# TrackerS_onecznyv2.net
KiCad netlist of a schematic drawn in EAGLE
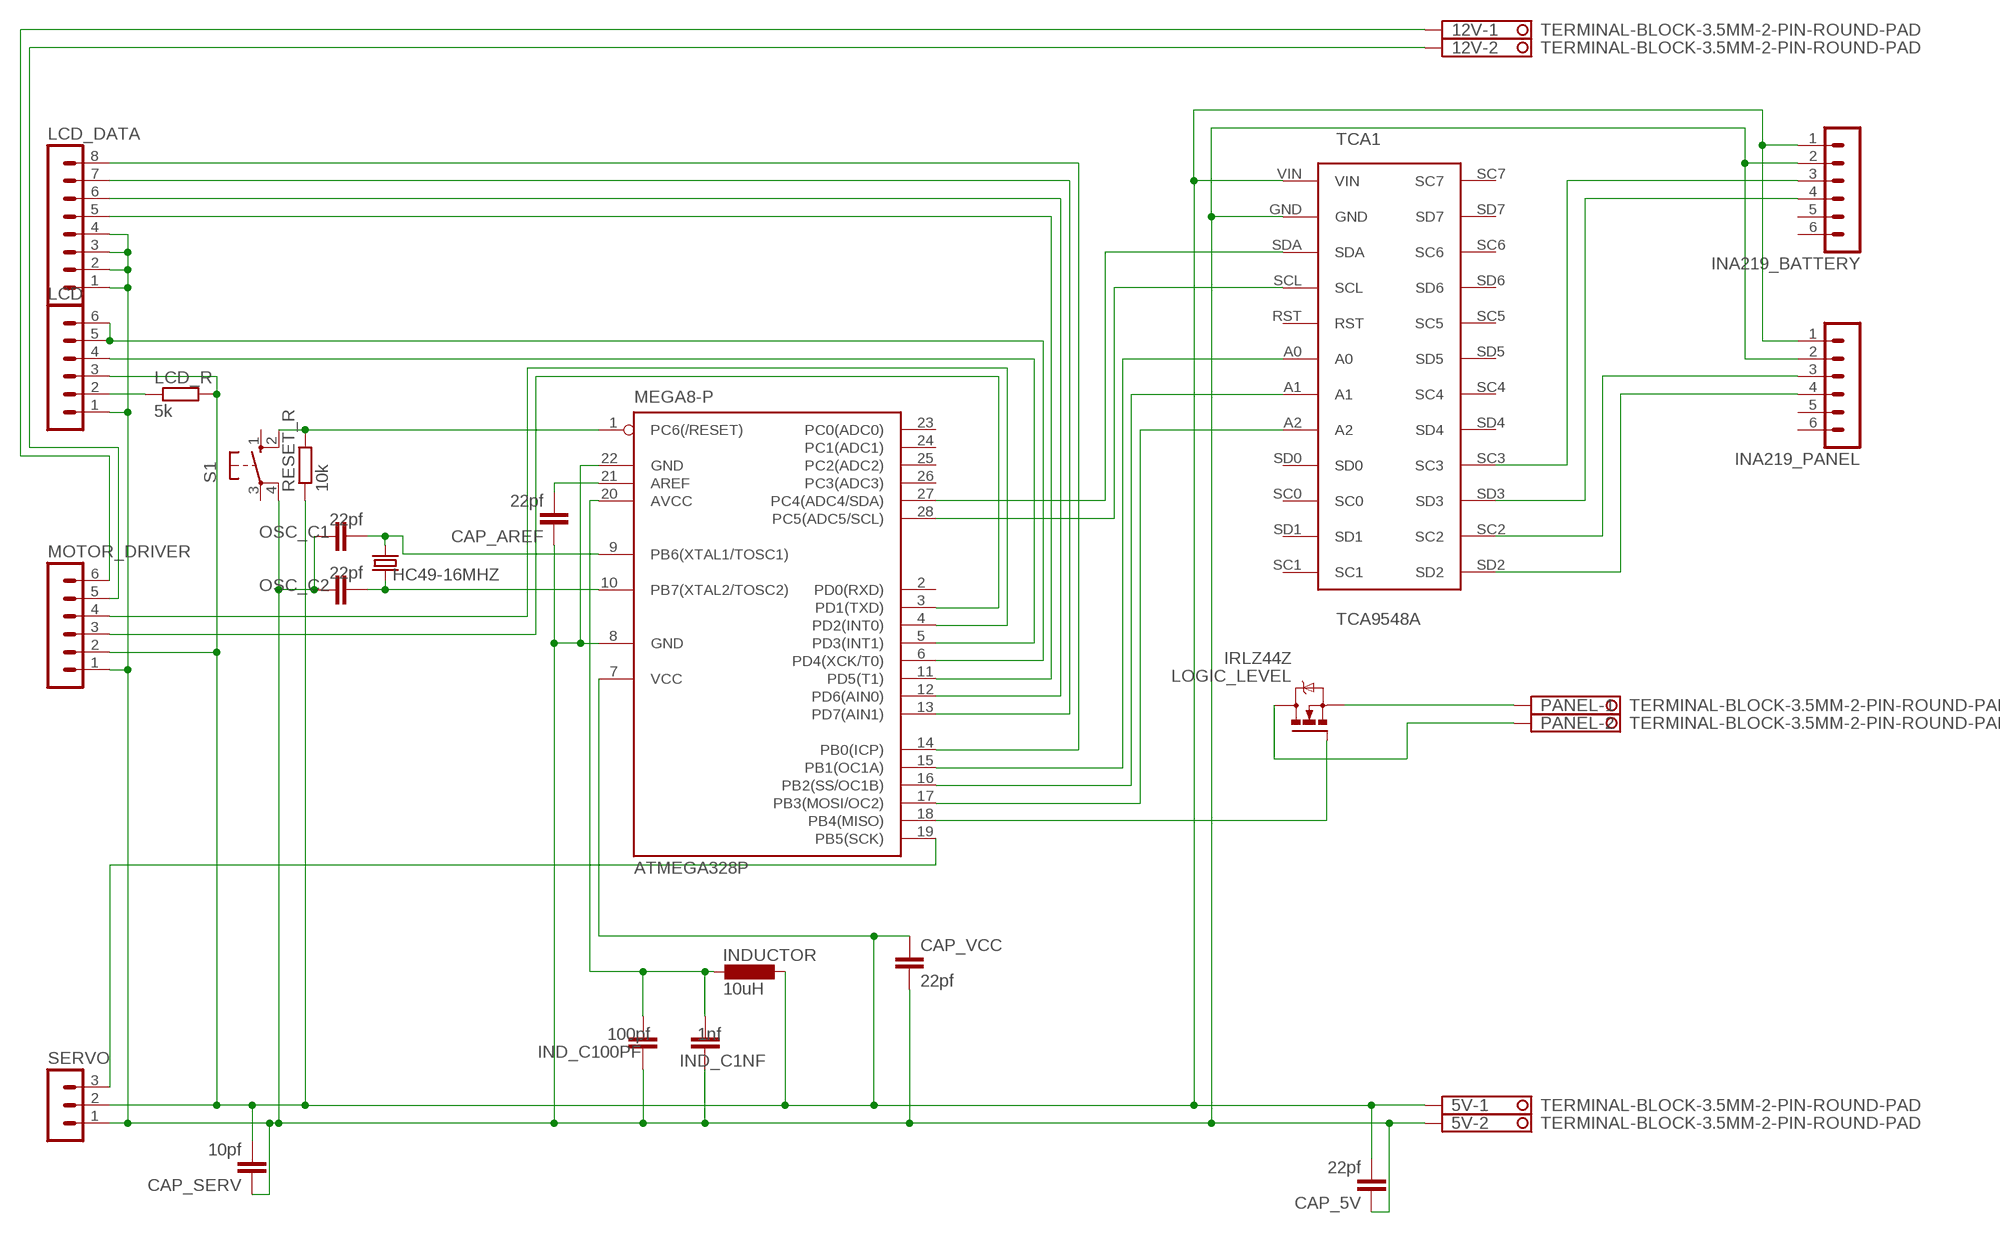
[diagram p0: schematic, sheet 1]

(export (version "E")
  (design (tool "Eeschema 10.0.6"))
  (components
    (comp (ref "5V")
      (value "TERMINAL-BLOCK-3.5MM-2-PIN-ROUND-PAD")
      (footprint "eagle-import:TERMINAL-BLOCK-2-PIN-3.5MM-ROUND-PAD")
      (libsource (lib "eagle-import") (part "TERMINAL-BLOCK-3.5MM-2-PIN-ROUND-PAD"))
    )
    (comp (ref "12V")
      (value "TERMINAL-BLOCK-3.5MM-2-PIN-ROUND-PAD")
      (footprint "eagle-import:TERMINAL-BLOCK-2-PIN-3.5MM-ROUND-PAD")
      (libsource (lib "eagle-import") (part "TERMINAL-BLOCK-3.5MM-2-PIN-ROUND-PAD"))
    )
    (comp (ref "ATMEGA328P")
      (value "MEGA8-P")
      (footprint "eagle-import:DIL28-3")
      (libsource (lib "eagle-import") (part "MEGA8-P"))
    )
    (comp (ref "CAP_5V")
      (value "22pf")
      (footprint "eagle-import:C025-024X044")
      (libsource (lib "eagle-import") (part "C-EU025-024X044"))
    )
    (comp (ref "CAP_AREF")
      (value "22pf")
      (footprint "eagle-import:C025-024X044")
      (libsource (lib "eagle-import") (part "C-EU025-024X044"))
    )
    (comp (ref "CAP_SERV")
      (value "10pf")
      (footprint "eagle-import:C025-024X044")
      (libsource (lib "eagle-import") (part "C-EU025-024X044"))
    )
    (comp (ref "CAP_VCC")
      (value "22pf")
      (footprint "eagle-import:C025-024X044")
      (libsource (lib "eagle-import") (part "C-EU025-024X044"))
    )
    (comp (ref "HC49-16MHZ")
      (value "CRYTALHC49S")
      (footprint "eagle-import:HC49_S")
      (libsource (lib "eagle-import") (part "CRYTALHC49S"))
    )
    (comp (ref "INA219_BATTERY")
      (value "MA06-1")
      (footprint "eagle-import:MA06-1")
      (libsource (lib "eagle-import") (part "con-lstb_162_MA06-1"))
    )
    (comp (ref "INA219_PANEL")
      (value "MA06-1")
      (footprint "eagle-import:MA06-1")
      (libsource (lib "eagle-import") (part "con-lstb_162_MA06-1"))
    )
    (comp (ref "INDUCTOR")
      (value "10uH")
      (footprint "eagle-import:0207_2V")
      (libsource (lib "eagle-import") (part "L-EU0207/2V"))
    )
    (comp (ref "IND_C1NF")
      (value "1nf")
      (footprint "eagle-import:C025-024X044")
      (libsource (lib "eagle-import") (part "C-EU025-024X044"))
    )
    (comp (ref "IND_C100PF")
      (value "100pf")
      (footprint "eagle-import:C025-024X044")
      (libsource (lib "eagle-import") (part "C-EU025-024X044"))
    )
    (comp (ref "LCD")
      (value "MA06-1")
      (footprint "eagle-import:MA06-1")
      (libsource (lib "eagle-import") (part "MA06-1"))
    )
    (comp (ref "LCD_DATA")
      (value "MA08-1")
      (footprint "eagle-import:MA08-1")
      (libsource (lib "eagle-import") (part "MA08-1"))
    )
    (comp (ref "LCD_R")
      (value "5k")
      (footprint "eagle-import:0207_2V")
      (libsource (lib "eagle-import") (part "R-EU_0207/2V"))
    )
    (comp (ref "LOGIC_LEVEL")
      (value "IRLZ44Z")
      (footprint "eagle-import:TO220BH")
      (libsource (lib "eagle-import") (part "IRLZ44Z"))
    )
    (comp (ref "MOTOR_DRIVER")
      (value "MA06-1")
      (footprint "eagle-import:MA06-1")
      (libsource (lib "eagle-import") (part "MA06-1"))
    )
    (comp (ref "OSC_C1")
      (value "22pf")
      (footprint "eagle-import:C025-024X044")
      (libsource (lib "eagle-import") (part "C-EU025-024X044"))
    )
    (comp (ref "OSC_C2")
      (value "22pf")
      (footprint "eagle-import:C025-024X044")
      (libsource (lib "eagle-import") (part "C-EU025-024X044"))
    )
    (comp (ref "PANEL")
      (value "TERMINAL-BLOCK-3.5MM-2-PIN-ROUND-PAD")
      (footprint "eagle-import:TERMINAL-BLOCK-2-PIN-3.5MM-ROUND-PAD")
      (libsource (lib "eagle-import") (part "TERMINAL-BLOCK-3.5MM-2-PIN-ROUND-PAD"))
    )
    (comp (ref "RESET_R")
      (value "10k")
      (footprint "eagle-import:0207_2V")
      (libsource (lib "eagle-import") (part "R-EU_0207/2V"))
    )
    (comp (ref "S1")
      (value "10-XX")
      (footprint "eagle-import:B3F-10XX")
      (fields (field (name "MPN") "B3F-1000"))
      (libsource (lib "eagle-import") (part "10-XX"))
    )
    (comp (ref "SERVO")
      (value "MA03-1")
      (footprint "eagle-import:MA03-1")
      (libsource (lib "eagle-import") (part "MA03-1"))
    )
    (comp (ref "TCA1")
      (value "TCA9548A")
      (footprint "eagle-import:TCA9548A")
      (libsource (lib "eagle-import") (part "TCA9548A"))
    )
  )
  (nets
    (net (code "1") (name "Net-(5VA-K)") (class "Default")
      (node (ref "5V") (pin "1") (pinfunction "K_1") (pintype "passive"))
      (node (ref "ATMEGA328P") (pin "7") (pinfunction "VCC_7") (pintype "power_in"))
      (node (ref "CAP_5V") (pin "2") (pinfunction "2_2") (pintype "passive"))
      (node (ref "CAP_SERV") (pin "2") (pinfunction "2_2") (pintype "passive"))
      (node (ref "CAP_VCC") (pin "1") (pinfunction "1_1") (pintype "passive"))
      (node (ref "INA219_BATTERY") (pin "1") (pinfunction "1_1") (pintype "passive"))
      (node (ref "INA219_PANEL") (pin "1") (pinfunction "1_1") (pintype "passive"))
      (node (ref "INDUCTOR") (pin "1") (pinfunction "1_1") (pintype "passive"))
      (node (ref "LCD") (pin "3") (pinfunction "3_3") (pintype "passive"))
      (node (ref "LCD_R") (pin "2") (pinfunction "2_2") (pintype "passive"))
      (node (ref "MOTOR_DRIVER") (pin "2") (pinfunction "2_2") (pintype "passive"))
      (node (ref "RESET_R") (pin "1") (pinfunction "1_1") (pintype "passive"))
      (node (ref "SERVO") (pin "2") (pinfunction "2_2") (pintype "passive"))
      (node (ref "TCA1") (pin "VIN") (pinfunction "VIN_VIN") (pintype "bidirectional"))
    )
    (net (code "2") (name "Net-(5VB-K)") (class "Default")
      (node (ref "5V") (pin "2") (pinfunction "K_2") (pintype "passive"))
      (node (ref "ATMEGA328P") (pin "22") (pinfunction "GND_22") (pintype "power_in"))
      (node (ref "ATMEGA328P") (pin "8") (pinfunction "GND_8") (pintype "power_in"))
      (node (ref "CAP_5V") (pin "1") (pinfunction "1_1") (pintype "passive"))
      (node (ref "CAP_AREF") (pin "1") (pinfunction "1_1") (pintype "passive"))
      (node (ref "CAP_SERV") (pin "1") (pinfunction "1_1") (pintype "passive"))
      (node (ref "CAP_VCC") (pin "2") (pinfunction "2_2") (pintype "passive"))
      (node (ref "INA219_BATTERY") (pin "2") (pinfunction "2_2") (pintype "passive"))
      (node (ref "INA219_PANEL") (pin "2") (pinfunction "2_2") (pintype "passive"))
      (node (ref "IND_C100PF") (pin "1") (pinfunction "1_1") (pintype "passive"))
      (node (ref "IND_C1NF") (pin "1") (pinfunction "1_1") (pintype "passive"))
      (node (ref "LCD") (pin "1") (pinfunction "1_1") (pintype "passive"))
      (node (ref "LCD_DATA") (pin "1") (pinfunction "1_1") (pintype "passive"))
      (node (ref "LCD_DATA") (pin "2") (pinfunction "2_2") (pintype "passive"))
      (node (ref "LCD_DATA") (pin "3") (pinfunction "3_3") (pintype "passive"))
      (node (ref "LCD_DATA") (pin "4") (pinfunction "4_4") (pintype "passive"))
      (node (ref "MOTOR_DRIVER") (pin "1") (pinfunction "1_1") (pintype "passive"))
      (node (ref "OSC_C1") (pin "1") (pinfunction "1_1") (pintype "passive"))
      (node (ref "OSC_C2") (pin "1") (pinfunction "1_1") (pintype "passive"))
      (node (ref "S1") (pin "4") (pinfunction "P1_4") (pintype "passive"))
      (node (ref "SERVO") (pin "1") (pinfunction "1_1") (pintype "passive"))
      (node (ref "TCA1") (pin "GND") (pinfunction "GND_GND") (pintype "bidirectional"))
    )
    (net (code "3") (name "Net-(12VA-K)") (class "Default")
      (node (ref "12V") (pin "1") (pinfunction "K_1") (pintype "passive"))
      (node (ref "MOTOR_DRIVER") (pin "6") (pinfunction "6_6") (pintype "passive"))
    )
    (net (code "4") (name "Net-(12VB-K)") (class "Default")
      (node (ref "12V") (pin "2") (pinfunction "K_2") (pintype "passive"))
      (node (ref "MOTOR_DRIVER") (pin "5") (pinfunction "5_5") (pintype "passive"))
    )
    (net (code "5") (name "Net-(ATMEGA328P-AREF)") (class "Default")
      (node (ref "ATMEGA328P") (pin "21") (pinfunction "AREF_21") (pintype "passive"))
      (node (ref "CAP_AREF") (pin "2") (pinfunction "2_2") (pintype "passive"))
    )
    (net (code "6") (name "Net-(ATMEGA328P-AVCC)") (class "Default")
      (node (ref "ATMEGA328P") (pin "20") (pinfunction "AVCC_20") (pintype "power_in"))
      (node (ref "INDUCTOR") (pin "2") (pinfunction "2_2") (pintype "passive"))
      (node (ref "IND_C100PF") (pin "2") (pinfunction "2_2") (pintype "passive"))
      (node (ref "IND_C1NF") (pin "2") (pinfunction "2_2") (pintype "passive"))
    )
    (net (code "7") (name "Net-(ATMEGA328P-PB0(ICP))") (class "Default")
      (node (ref "ATMEGA328P") (pin "14") (pinfunction "PB0(ICP)_14") (pintype "bidirectional"))
      (node (ref "LCD_DATA") (pin "8") (pinfunction "8_8") (pintype "passive"))
    )
    (net (code "8") (name "Net-(ATMEGA328P-PB1(OC1A))") (class "Default")
      (node (ref "ATMEGA328P") (pin "15") (pinfunction "PB1(OC1A)_15") (pintype "bidirectional"))
      (node (ref "TCA1") (pin "A0") (pinfunction "A0_A0") (pintype "bidirectional"))
    )
    (net (code "9") (name "Net-(ATMEGA328P-PB2(SS{slash}OC1B))") (class "Default")
      (node (ref "ATMEGA328P") (pin "16") (pinfunction "PB2(SS/OC1B)_16") (pintype "bidirectional"))
      (node (ref "TCA1") (pin "A1") (pinfunction "A1_A1") (pintype "bidirectional"))
    )
    (net (code "10") (name "Net-(ATMEGA328P-PB3(MOSI{slash}OC2))") (class "Default")
      (node (ref "ATMEGA328P") (pin "17") (pinfunction "PB3(MOSI/OC2)_17") (pintype "bidirectional"))
      (node (ref "TCA1") (pin "A2") (pinfunction "A2_A2") (pintype "bidirectional"))
    )
    (net (code "11") (name "Net-(ATMEGA328P-PB4(MISO))") (class "Default")
      (node (ref "ATMEGA328P") (pin "18") (pinfunction "PB4(MISO)_18") (pintype "bidirectional"))
      (node (ref "LOGIC_LEVEL") (pin "G") (pinfunction "G_G") (pintype "passive"))
    )
    (net (code "12") (name "Net-(ATMEGA328P-PB5(SCK))") (class "Default")
      (node (ref "ATMEGA328P") (pin "19") (pinfunction "PB5(SCK)_19") (pintype "bidirectional"))
      (node (ref "SERVO") (pin "3") (pinfunction "3_3") (pintype "passive"))
    )
    (net (code "13") (name "Net-(ATMEGA328P-PB6(XTAL1{slash}TOSC1))") (class "Default")
      (node (ref "ATMEGA328P") (pin "9") (pinfunction "PB6(XTAL1/TOSC1)_9") (pintype "bidirectional"))
      (node (ref "HC49-16MHZ") (pin "1") (pinfunction "1_1") (pintype "passive"))
      (node (ref "OSC_C1") (pin "2") (pinfunction "2_2") (pintype "passive"))
    )
    (net (code "14") (name "Net-(ATMEGA328P-PB7(XTAL2{slash}TOSC2))") (class "Default")
      (node (ref "ATMEGA328P") (pin "10") (pinfunction "PB7(XTAL2/TOSC2)_10") (pintype "bidirectional"))
      (node (ref "HC49-16MHZ") (pin "2") (pinfunction "2_2") (pintype "passive"))
      (node (ref "OSC_C2") (pin "2") (pinfunction "2_2") (pintype "passive"))
    )
    (net (code "15") (name "Net-(ATMEGA328P-PC4(ADC4{slash}SDA))") (class "Default")
      (node (ref "ATMEGA328P") (pin "27") (pinfunction "PC4(ADC4/SDA)_27") (pintype "bidirectional"))
      (node (ref "TCA1") (pin "SDA") (pinfunction "SDA_SDA") (pintype "bidirectional"))
    )
    (net (code "16") (name "Net-(ATMEGA328P-PC5(ADC5{slash}SCL))") (class "Default")
      (node (ref "ATMEGA328P") (pin "28") (pinfunction "PC5(ADC5/SCL)_28") (pintype "bidirectional"))
      (node (ref "TCA1") (pin "SCL") (pinfunction "SCL_SCL") (pintype "bidirectional"))
    )
    (net (code "17") (name "Net-(ATMEGA328P-PC6({slash}RESET))") (class "Default")
      (node (ref "ATMEGA328P") (pin "1") (pinfunction "PC6(/RESET)_1") (pintype "bidirectional"))
      (node (ref "RESET_R") (pin "2") (pinfunction "2_2") (pintype "passive"))
      (node (ref "S1") (pin "2") (pinfunction "S1_2") (pintype "passive"))
    )
    (net (code "18") (name "Net-(ATMEGA328P-PD1(TXD))") (class "Default")
      (node (ref "ATMEGA328P") (pin "3") (pinfunction "PD1(TXD)_3") (pintype "bidirectional"))
      (node (ref "MOTOR_DRIVER") (pin "3") (pinfunction "3_3") (pintype "passive"))
    )
    (net (code "19") (name "Net-(ATMEGA328P-PD2(INT0))") (class "Default")
      (node (ref "ATMEGA328P") (pin "4") (pinfunction "PD2(INT0)_4") (pintype "bidirectional"))
      (node (ref "MOTOR_DRIVER") (pin "4") (pinfunction "4_4") (pintype "passive"))
    )
    (net (code "20") (name "Net-(ATMEGA328P-PD3(INT1))") (class "Default")
      (node (ref "ATMEGA328P") (pin "5") (pinfunction "PD3(INT1)_5") (pintype "bidirectional"))
      (node (ref "LCD") (pin "4") (pinfunction "4_4") (pintype "passive"))
    )
    (net (code "21") (name "Net-(ATMEGA328P-PD4(XCK{slash}T0))") (class "Default")
      (node (ref "ATMEGA328P") (pin "6") (pinfunction "PD4(XCK/T0)_6") (pintype "bidirectional"))
      (node (ref "LCD") (pin "5") (pinfunction "5_5") (pintype "passive"))
      (node (ref "LCD") (pin "6") (pinfunction "6_6") (pintype "passive"))
    )
    (net (code "22") (name "Net-(ATMEGA328P-PD5(T1))") (class "Default")
      (node (ref "ATMEGA328P") (pin "11") (pinfunction "PD5(T1)_11") (pintype "bidirectional"))
      (node (ref "LCD_DATA") (pin "5") (pinfunction "5_5") (pintype "passive"))
    )
    (net (code "23") (name "Net-(ATMEGA328P-PD6(AIN0))") (class "Default")
      (node (ref "ATMEGA328P") (pin "12") (pinfunction "PD6(AIN0)_12") (pintype "bidirectional"))
      (node (ref "LCD_DATA") (pin "6") (pinfunction "6_6") (pintype "passive"))
    )
    (net (code "24") (name "Net-(ATMEGA328P-PD7(AIN1))") (class "Default")
      (node (ref "ATMEGA328P") (pin "13") (pinfunction "PD7(AIN1)_13") (pintype "bidirectional"))
      (node (ref "LCD_DATA") (pin "7") (pinfunction "7_7") (pintype "passive"))
    )
    (net (code "25") (name "Net-(INA219_BATTERY-Pad3)") (class "Default")
      (node (ref "INA219_BATTERY") (pin "3") (pinfunction "3_3") (pintype "passive"))
      (node (ref "TCA1") (pin "SC3") (pinfunction "SC3_SC3") (pintype "bidirectional"))
    )
    (net (code "26") (name "Net-(INA219_BATTERY-Pad4)") (class "Default")
      (node (ref "INA219_BATTERY") (pin "4") (pinfunction "4_4") (pintype "passive"))
      (node (ref "TCA1") (pin "SD3") (pinfunction "SD3_SD3") (pintype "bidirectional"))
    )
    (net (code "27") (name "Net-(INA219_PANEL-Pad3)") (class "Default")
      (node (ref "INA219_PANEL") (pin "3") (pinfunction "3_3") (pintype "passive"))
      (node (ref "TCA1") (pin "SC2") (pinfunction "SC2_SC2") (pintype "bidirectional"))
    )
    (net (code "28") (name "Net-(INA219_PANEL-Pad4)") (class "Default")
      (node (ref "INA219_PANEL") (pin "4") (pinfunction "4_4") (pintype "passive"))
      (node (ref "TCA1") (pin "SD2") (pinfunction "SD2_SD2") (pintype "bidirectional"))
    )
    (net (code "29") (name "Net-(LCD-Pad2)") (class "Default")
      (node (ref "LCD") (pin "2") (pinfunction "2_2") (pintype "passive"))
      (node (ref "LCD_R") (pin "1") (pinfunction "1_1") (pintype "passive"))
    )
    (net (code "30") (name "Net-(PANELA-K)") (class "Default")
      (node (ref "LOGIC_LEVEL") (pin "S") (pinfunction "S_S") (pintype "passive"))
      (node (ref "PANEL") (pin "1") (pinfunction "K_1") (pintype "passive"))
    )
    (net (code "31") (name "Net-(PANELB-K)") (class "Default")
      (node (ref "LOGIC_LEVEL") (pin "D") (pinfunction "D_D") (pintype "passive"))
      (node (ref "PANEL") (pin "2") (pinfunction "K_2") (pintype "passive"))
    )
    (net (code "32") (name "unconnected-(ATMEGA328P-PC0(ADC0)-Pad23)") (class "Default")
      (node (ref "ATMEGA328P") (pin "23") (pinfunction "PC0(ADC0)_23") (pintype "bidirectional"))
    )
    (net (code "33") (name "unconnected-(ATMEGA328P-PC1(ADC1)-Pad24)") (class "Default")
      (node (ref "ATMEGA328P") (pin "24") (pinfunction "PC1(ADC1)_24") (pintype "bidirectional"))
    )
    (net (code "34") (name "unconnected-(ATMEGA328P-PC2(ADC2)-Pad25)") (class "Default")
      (node (ref "ATMEGA328P") (pin "25") (pinfunction "PC2(ADC2)_25") (pintype "bidirectional"))
    )
    (net (code "35") (name "unconnected-(ATMEGA328P-PC3(ADC3)-Pad26)") (class "Default")
      (node (ref "ATMEGA328P") (pin "26") (pinfunction "PC3(ADC3)_26") (pintype "bidirectional"))
    )
    (net (code "36") (name "unconnected-(ATMEGA328P-PD0(RXD)-Pad2)") (class "Default")
      (node (ref "ATMEGA328P") (pin "2") (pinfunction "PD0(RXD)_2") (pintype "bidirectional"))
    )
    (net (code "37") (name "unconnected-(INA219_BATTERY-Pad5)") (class "Default")
      (node (ref "INA219_BATTERY") (pin "5") (pinfunction "5_5") (pintype "passive"))
    )
    (net (code "38") (name "unconnected-(INA219_BATTERY-Pad6)") (class "Default")
      (node (ref "INA219_BATTERY") (pin "6") (pinfunction "6_6") (pintype "passive"))
    )
    (net (code "39") (name "unconnected-(INA219_PANEL-Pad5)") (class "Default")
      (node (ref "INA219_PANEL") (pin "5") (pinfunction "5_5") (pintype "passive"))
    )
    (net (code "40") (name "unconnected-(INA219_PANEL-Pad6)") (class "Default")
      (node (ref "INA219_PANEL") (pin "6") (pinfunction "6_6") (pintype "passive"))
    )
    (net (code "41") (name "unconnected-(S1-P-Pad3)") (class "Default")
      (node (ref "S1") (pin "3") (pinfunction "P_3") (pintype "passive"))
    )
    (net (code "42") (name "unconnected-(S1-S-Pad1)") (class "Default")
      (node (ref "S1") (pin "1") (pinfunction "S_1") (pintype "passive"))
    )
    (net (code "43") (name "unconnected-(TCA1-PadRST)") (class "Default")
      (node (ref "TCA1") (pin "RST") (pinfunction "RST_RST") (pintype "bidirectional"))
    )
    (net (code "44") (name "unconnected-(TCA1-PadSC0)") (class "Default")
      (node (ref "TCA1") (pin "SC0") (pinfunction "SC0_SC0") (pintype "bidirectional"))
    )
    (net (code "45") (name "unconnected-(TCA1-PadSC1)") (class "Default")
      (node (ref "TCA1") (pin "SC1") (pinfunction "SC1_SC1") (pintype "bidirectional"))
    )
    (net (code "46") (name "unconnected-(TCA1-PadSC4)") (class "Default")
      (node (ref "TCA1") (pin "SC4") (pinfunction "SC4_SC4") (pintype "bidirectional"))
    )
    (net (code "47") (name "unconnected-(TCA1-PadSC5)") (class "Default")
      (node (ref "TCA1") (pin "SC5") (pinfunction "SC5_SC5") (pintype "bidirectional"))
    )
    (net (code "48") (name "unconnected-(TCA1-PadSC6)") (class "Default")
      (node (ref "TCA1") (pin "SC6") (pinfunction "SC6_SC6") (pintype "bidirectional"))
    )
    (net (code "49") (name "unconnected-(TCA1-PadSC7)") (class "Default")
      (node (ref "TCA1") (pin "SC7") (pinfunction "SC7_SC7") (pintype "bidirectional"))
    )
    (net (code "50") (name "unconnected-(TCA1-PadSD0)") (class "Default")
      (node (ref "TCA1") (pin "SD0") (pinfunction "SD0_SD0") (pintype "bidirectional"))
    )
    (net (code "51") (name "unconnected-(TCA1-PadSD1)") (class "Default")
      (node (ref "TCA1") (pin "SD1") (pinfunction "SD1_SD1") (pintype "bidirectional"))
    )
    (net (code "52") (name "unconnected-(TCA1-PadSD4)") (class "Default")
      (node (ref "TCA1") (pin "SD4") (pinfunction "SD4_SD4") (pintype "bidirectional"))
    )
    (net (code "53") (name "unconnected-(TCA1-PadSD5)") (class "Default")
      (node (ref "TCA1") (pin "SD5") (pinfunction "SD5_SD5") (pintype "bidirectional"))
    )
    (net (code "54") (name "unconnected-(TCA1-PadSD6)") (class "Default")
      (node (ref "TCA1") (pin "SD6") (pinfunction "SD6_SD6") (pintype "bidirectional"))
    )
    (net (code "55") (name "unconnected-(TCA1-PadSD7)") (class "Default")
      (node (ref "TCA1") (pin "SD7") (pinfunction "SD7_SD7") (pintype "bidirectional"))
    )
  )
)
